# Buttons.net
KiCad netlist of a schematic drawn in Altium Designer
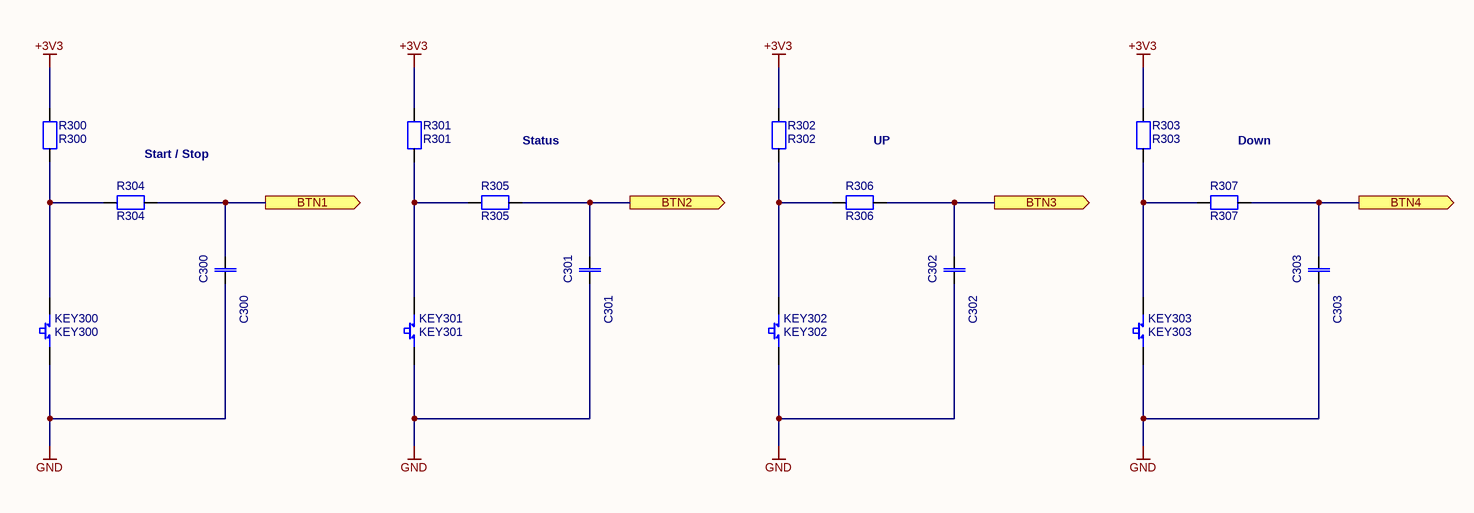
[diagram p0: Buttons.SchDoc]

(export (version "E")
  (design (tool "Eeschema 10.0.6"))
  (components
    (comp (ref "C300")
      (value "C 100nF 50V X7R")
      (footprint "0603-1608")
      (description "Capacitor")
      (fields
        (field (name "MANUFACTURER") "KEMET")
        (field (name "MANUFACTURER PART NUMBER") "C0603C104K5RACTU")
      )
      (libsource (lib "Database_Libs1") (part "Kondensator"))
    )
    (comp (ref "C301")
      (value "C 100nF 50V X7R")
      (footprint "0603-1608")
      (description "Capacitor")
      (fields
        (field (name "MANUFACTURER") "KEMET")
        (field (name "MANUFACTURER PART NUMBER") "C0603C104K5RACTU")
      )
      (libsource (lib "Database_Libs1") (part "Kondensator"))
    )
    (comp (ref "C302")
      (value "C 100nF 50V X7R")
      (footprint "0603-1608")
      (description "Capacitor")
      (fields
        (field (name "MANUFACTURER") "KEMET")
        (field (name "MANUFACTURER PART NUMBER") "C0603C104K5RACTU")
      )
      (libsource (lib "Database_Libs1") (part "Kondensator"))
    )
    (comp (ref "C303")
      (value "C 100nF 50V X7R")
      (footprint "0603-1608")
      (description "Capacitor")
      (fields
        (field (name "MANUFACTURER") "KEMET")
        (field (name "MANUFACTURER PART NUMBER") "C0603C104K5RACTU")
      )
      (libsource (lib "Database_Libs1") (part "Kondensator"))
    )
    (comp (ref "KEY300")
      (value "TL9210AF180Q")
      (footprint "SW_TL9210AF180Q")
      (description "Button")
      (fields (field (name "MANUFACTURER") "E-Switch"))
      (libsource (lib "Database_Libs1") (part "Drucktaste"))
    )
    (comp (ref "KEY301")
      (value "TL9210AF180Q")
      (footprint "SW_TL9210AF180Q")
      (description "Button")
      (fields (field (name "MANUFACTURER") "E-Switch"))
      (libsource (lib "Database_Libs1") (part "Drucktaste"))
    )
    (comp (ref "KEY302")
      (value "TL9210AF180Q")
      (footprint "SW_TL9210AF180Q")
      (description "Button")
      (fields (field (name "MANUFACTURER") "E-Switch"))
      (libsource (lib "Database_Libs1") (part "Drucktaste"))
    )
    (comp (ref "KEY303")
      (value "TL9210AF180Q")
      (footprint "SW_TL9210AF180Q")
      (description "Button")
      (fields (field (name "MANUFACTURER") "E-Switch"))
      (libsource (lib "Database_Libs1") (part "Drucktaste"))
    )
    (comp (ref "R300")
      (value "R 10k 1%")
      (footprint "0603-1608")
      (description "Resistor")
      (fields
        (field (name "MANUFACTURER") "Vishay Dale")
        (field (name "MANUFACTURER PART NUMBER") "CRCW060310K0FKEAHP")
        (field (name "VERIFICATION") "05.07.2012 OPT")
      )
      (libsource (lib "Database_Libs1") (part "Resistor"))
    )
    (comp (ref "R301")
      (value "R 10k 1%")
      (footprint "0603-1608")
      (description "Resistor")
      (fields
        (field (name "MANUFACTURER") "Vishay Dale")
        (field (name "MANUFACTURER PART NUMBER") "CRCW060310K0FKEAHP")
        (field (name "VERIFICATION") "05.07.2012 OPT")
      )
      (libsource (lib "Database_Libs1") (part "Resistor"))
    )
    (comp (ref "R302")
      (value "R 10k 1%")
      (footprint "0603-1608")
      (description "Resistor")
      (fields
        (field (name "MANUFACTURER") "Vishay Dale")
        (field (name "MANUFACTURER PART NUMBER") "CRCW060310K0FKEAHP")
        (field (name "VERIFICATION") "05.07.2012 OPT")
      )
      (libsource (lib "Database_Libs1") (part "Resistor"))
    )
    (comp (ref "R303")
      (value "R 10k 1%")
      (footprint "0603-1608")
      (description "Resistor")
      (fields
        (field (name "MANUFACTURER") "Vishay Dale")
        (field (name "MANUFACTURER PART NUMBER") "CRCW060310K0FKEAHP")
        (field (name "VERIFICATION") "05.07.2012 OPT")
      )
      (libsource (lib "Database_Libs1") (part "Resistor"))
    )
    (comp (ref "R304")
      (value "R 100E 1%")
      (footprint "0603-1608")
      (description "Resistor")
      (fields
        (field (name "MANUFACTURER") "Vishay Dale")
        (field (name "MANUFACTURER PART NUMBER") "CRCW0603100RFKEA")
        (field (name "VERIFICATION") "05.07.2012 OPT")
      )
      (libsource (lib "Database_Libs1") (part "Resistor"))
    )
    (comp (ref "R305")
      (value "R 100E 1%")
      (footprint "0603-1608")
      (description "Resistor")
      (fields
        (field (name "MANUFACTURER") "Vishay Dale")
        (field (name "MANUFACTURER PART NUMBER") "CRCW0603100RFKEA")
        (field (name "VERIFICATION") "05.07.2012 OPT")
      )
      (libsource (lib "Database_Libs1") (part "Resistor"))
    )
    (comp (ref "R306")
      (value "R 100E 1%")
      (footprint "0603-1608")
      (description "Resistor")
      (fields
        (field (name "MANUFACTURER") "Vishay Dale")
        (field (name "MANUFACTURER PART NUMBER") "CRCW0603100RFKEA")
        (field (name "VERIFICATION") "05.07.2012 OPT")
      )
      (libsource (lib "Database_Libs1") (part "Resistor"))
    )
    (comp (ref "R307")
      (value "R 100E 1%")
      (footprint "0603-1608")
      (description "Resistor")
      (fields
        (field (name "MANUFACTURER") "Vishay Dale")
        (field (name "MANUFACTURER PART NUMBER") "CRCW0603100RFKEA")
        (field (name "VERIFICATION") "05.07.2012 OPT")
      )
      (libsource (lib "Database_Libs1") (part "Resistor"))
    )
  )
  (nets
    (net (code "1") (name "+3V3") (class "Default")
      (node (ref "R300") (pin "1") (pinfunction "1_1") (pintype "passive"))
      (node (ref "R301") (pin "1") (pinfunction "1_1") (pintype "passive"))
      (node (ref "R302") (pin "1") (pinfunction "1_1") (pintype "passive"))
      (node (ref "R303") (pin "1") (pinfunction "1_1") (pintype "passive"))
    )
    (net (code "2") (name "/BTN1") (class "Default")
      (node (ref "C300") (pin "1") (pinfunction "1_1") (pintype "passive"))
      (node (ref "R304") (pin "2") (pinfunction "2_2") (pintype "passive"))
    )
    (net (code "3") (name "/BTN2") (class "Default")
      (node (ref "C301") (pin "1") (pinfunction "1_1") (pintype "passive"))
      (node (ref "R305") (pin "2") (pinfunction "2_2") (pintype "passive"))
    )
    (net (code "4") (name "/BTN3") (class "Default")
      (node (ref "C302") (pin "1") (pinfunction "1_1") (pintype "passive"))
      (node (ref "R306") (pin "2") (pinfunction "2_2") (pintype "passive"))
    )
    (net (code "5") (name "/BTN4") (class "Default")
      (node (ref "C303") (pin "1") (pinfunction "1_1") (pintype "passive"))
      (node (ref "R307") (pin "2") (pinfunction "2_2") (pintype "passive"))
    )
    (net (code "6") (name "GND") (class "Default")
      (node (ref "C300") (pin "2") (pinfunction "2_2") (pintype "passive"))
      (node (ref "C301") (pin "2") (pinfunction "2_2") (pintype "passive"))
      (node (ref "C302") (pin "2") (pinfunction "2_2") (pintype "passive"))
      (node (ref "C303") (pin "2") (pinfunction "2_2") (pintype "passive"))
      (node (ref "KEY300") (pin "1") (pintype "passive"))
      (node (ref "KEY301") (pin "1") (pintype "passive"))
      (node (ref "KEY302") (pin "1") (pintype "passive"))
      (node (ref "KEY303") (pin "1") (pintype "passive"))
    )
    (net (code "7") (name "Net-(KEY300-Pad2)") (class "Default")
      (node (ref "KEY300") (pin "2") (pintype "passive"))
      (node (ref "R300") (pin "2") (pinfunction "2_2") (pintype "passive"))
      (node (ref "R304") (pin "1") (pinfunction "1_1") (pintype "passive"))
    )
    (net (code "8") (name "Net-(KEY301-Pad2)") (class "Default")
      (node (ref "KEY301") (pin "2") (pintype "passive"))
      (node (ref "R301") (pin "2") (pinfunction "2_2") (pintype "passive"))
      (node (ref "R305") (pin "1") (pinfunction "1_1") (pintype "passive"))
    )
    (net (code "9") (name "Net-(KEY302-Pad2)") (class "Default")
      (node (ref "KEY302") (pin "2") (pintype "passive"))
      (node (ref "R302") (pin "2") (pinfunction "2_2") (pintype "passive"))
      (node (ref "R306") (pin "1") (pinfunction "1_1") (pintype "passive"))
    )
    (net (code "10") (name "Net-(KEY303-Pad2)") (class "Default")
      (node (ref "KEY303") (pin "2") (pintype "passive"))
      (node (ref "R303") (pin "2") (pinfunction "2_2") (pintype "passive"))
      (node (ref "R307") (pin "1") (pinfunction "1_1") (pintype "passive"))
    )
  )
)
